# 24_063.net
KiCad netlist of a schematic drawn in Altium Designer
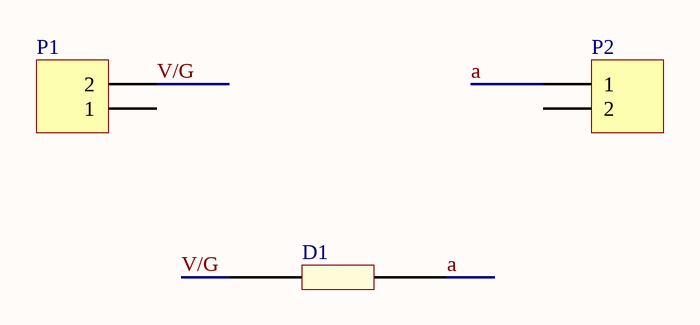
[diagram p0: 24.063.SchDoc]

(export (version "E")
  (design (tool "Eeschema 10.0.6"))
  (components
    (comp (ref "D1") (value "resistor") (footprint "RES 1608?") (libsource (lib "msp_SchLib") (part "RES")))
    (comp (ref "P1")
      (value "Header 2")
      (footprint "HDR1X2")
      (description "Header, 2-Pin")
      (fields (field (name "PUBLISHER") "Altium Limited"))
      (libsource (lib "Miscellaneous Connectors") (part "Header 2"))
    )
    (comp (ref "P2")
      (value "Header 2")
      (footprint "HDR1X2")
      (description "Header, 2-Pin")
      (fields (field (name "PUBLISHER") "Altium Limited"))
      (libsource (lib "") (part "Header 2_1"))
    )
  )
  (nets
    (net (code "1") (name "/V{slash}G") (class "Default")
      (node (ref "D1") (pin "1") (pinfunction "1_1") (pintype "passive"))
      (node (ref "P1") (pin "2") (pinfunction "2_2") (pintype "passive"))
    )
    (net (code "2") (name "/a") (class "Default")
      (node (ref "D1") (pin "2") (pinfunction "2_2") (pintype "passive"))
      (node (ref "P2") (pin "1") (pinfunction "1_1") (pintype "passive"))
    )
    (net (code "3") (name "unconnected-(P1-Pad1)") (class "Default")
      (node (ref "P1") (pin "1") (pinfunction "1_1") (pintype "passive"))
    )
    (net (code "4") (name "unconnected-(P2-Pad2)") (class "Default")
      (node (ref "P2") (pin "2") (pinfunction "2_2") (pintype "passive"))
    )
  )
)
